# power_card_24_rev2.net
KiCad netlist of a schematic drawn in EAGLE
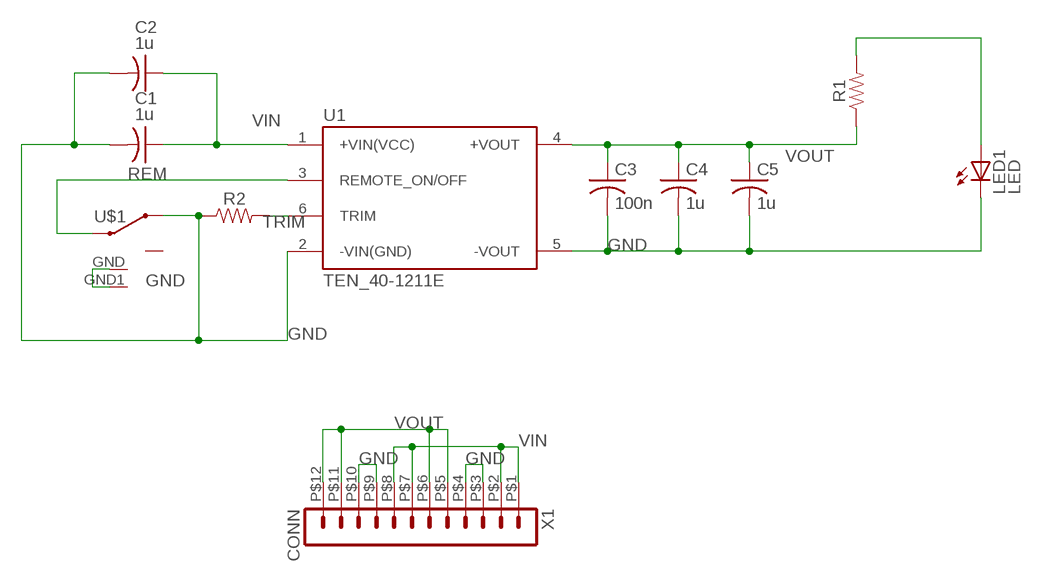
[diagram p0: schematic, sheet 1]

(export (version "E")
  (design (tool "Eeschema 10.0.6"))
  (components
    (comp (ref "C1")
      (value "1u")
      (footprint "eagle-import:C1206")
      (libsource (lib "eagle-import") (part "C-USC1206"))
    )
    (comp (ref "C2")
      (value "1u")
      (footprint "eagle-import:C1206")
      (libsource (lib "eagle-import") (part "C-USC1206"))
    )
    (comp (ref "C3")
      (value "100n")
      (footprint "eagle-import:C1206")
      (libsource (lib "eagle-import") (part "C-USC1206"))
    )
    (comp (ref "C4")
      (value "1u")
      (footprint "eagle-import:C1206")
      (libsource (lib "eagle-import") (part "C-USC1206"))
    )
    (comp (ref "C5")
      (value "1u")
      (footprint "eagle-import:C1206")
      (libsource (lib "eagle-import") (part "C-USC1206"))
    )
    (comp (ref "LED1")
      (value "LED")
      (footprint "eagle-import:LED5MM")
      (libsource (lib "eagle-import") (part "LED5MM"))
    )
    (comp (ref "R1")
      (value "RESISTOR1206")
      (footprint "eagle-import:1206")
      (libsource (lib "eagle-import") (part "RESISTOR1206"))
    )
    (comp (ref "R2")
      (value "RESISTOR1206")
      (footprint "eagle-import:1206")
      (libsource (lib "eagle-import") (part "RESISTOR1206"))
    )
    (comp (ref "U$1")
      (value "1825232-1")
      (footprint "eagle-import:1825232-1")
      (fields (field (name "MF") "TE Connectivity"))
      (libsource (lib "eagle-import") (part "1825232-1"))
    )
    (comp (ref "U1")
      (value "TEN_40-1211E")
      (footprint "eagle-import:CONV_TEN_40-1211E")
      (fields (field (name "MF") "Traco Power") (field (name "MP") "TEN 40-1211E"))
      (libsource (lib "eagle-import") (part "TEN_40-1211E"))
    )
    (comp (ref "X1")
      (value "CONN")
      (footprint "eagle-import:44764-1201")
      (libsource (lib "eagle-import") (part "HEADER_POS12_?44764-1201"))
    )
  )
  (nets
    (net (code "1") (name "/GND") (class "Default")
      (node (ref "C1") (pin "2") (pinfunction "2_2") (pintype "passive"))
      (node (ref "C2") (pin "2") (pinfunction "2_2") (pintype "passive"))
      (node (ref "C3") (pin "2") (pinfunction "2_2") (pintype "passive"))
      (node (ref "C4") (pin "2") (pinfunction "2_2") (pintype "passive"))
      (node (ref "C5") (pin "2") (pinfunction "2_2") (pintype "passive"))
      (node (ref "LED1") (pin "K") (pinfunction "C_K") (pintype "passive"))
      (node (ref "R2") (pin "1") (pinfunction "1_1") (pintype "passive"))
      (node (ref "U$1") (pin "3") (pinfunction "3_3") (pintype "passive"))
      (node (ref "U$1") (pin "GND") (pinfunction "GND_GND") (pintype "passive"))
      (node (ref "U$1") (pin "GND1") (pinfunction "GND1_GND1") (pintype "passive"))
      (node (ref "U1") (pin "2") (pinfunction "-VIN(GND)_2") (pintype "input"))
      (node (ref "U1") (pin "5") (pinfunction "-VOUT_5") (pintype "output"))
      (node (ref "X1") (pin "P$10") (pinfunction "10_P$10") (pintype "passive"))
      (node (ref "X1") (pin "P$3") (pinfunction "3_P$3") (pintype "passive"))
      (node (ref "X1") (pin "P$4") (pinfunction "4_P$4") (pintype "passive"))
      (node (ref "X1") (pin "P$9") (pinfunction "9_P$9") (pintype "passive"))
    )
    (net (code "2") (name "/REM") (class "Default")
      (node (ref "U$1") (pin "2") (pinfunction "2_2") (pintype "passive"))
      (node (ref "U1") (pin "3") (pinfunction "REMOTE_ON/OFF_3") (pintype "input"))
    )
    (net (code "3") (name "/TRIM") (class "Default")
      (node (ref "R2") (pin "2") (pinfunction "2_2") (pintype "passive"))
      (node (ref "U1") (pin "6") (pinfunction "TRIM_6") (pintype "input"))
    )
    (net (code "4") (name "/VIN") (class "Default")
      (node (ref "C1") (pin "1") (pinfunction "1_1") (pintype "passive"))
      (node (ref "C2") (pin "1") (pinfunction "1_1") (pintype "passive"))
      (node (ref "U1") (pin "1") (pinfunction "+VIN(VCC)_1") (pintype "input"))
      (node (ref "X1") (pin "P$1") (pinfunction "1_P$1") (pintype "passive"))
      (node (ref "X1") (pin "P$2") (pinfunction "2_P$2") (pintype "passive"))
      (node (ref "X1") (pin "P$7") (pinfunction "7_P$7") (pintype "passive"))
      (node (ref "X1") (pin "P$8") (pinfunction "8_P$8") (pintype "passive"))
    )
    (net (code "5") (name "/VOUT") (class "Default")
      (node (ref "C3") (pin "1") (pinfunction "1_1") (pintype "passive"))
      (node (ref "C4") (pin "1") (pinfunction "1_1") (pintype "passive"))
      (node (ref "C5") (pin "1") (pinfunction "1_1") (pintype "passive"))
      (node (ref "R1") (pin "1") (pinfunction "1_1") (pintype "passive"))
      (node (ref "U1") (pin "4") (pinfunction "+VOUT_4") (pintype "output"))
      (node (ref "X1") (pin "P$11") (pinfunction "11_P$11") (pintype "passive"))
      (node (ref "X1") (pin "P$12") (pinfunction "12_P$12") (pintype "passive"))
      (node (ref "X1") (pin "P$5") (pinfunction "5_P$5") (pintype "passive"))
      (node (ref "X1") (pin "P$6") (pinfunction "6_P$6") (pintype "passive"))
    )
    (net (code "6") (name "Net-(LED1-PadA)") (class "Default")
      (node (ref "LED1") (pin "A") (pinfunction "A_A") (pintype "passive"))
      (node (ref "R1") (pin "2") (pinfunction "2_2") (pintype "passive"))
    )
    (net (code "7") (name "unconnected-(U$1-Pad1)") (class "Default")
      (node (ref "U$1") (pin "1") (pinfunction "1_1") (pintype "passive"))
    )
  )
)
